# Analog.net
KiCad netlist of a schematic drawn in Altium Designer
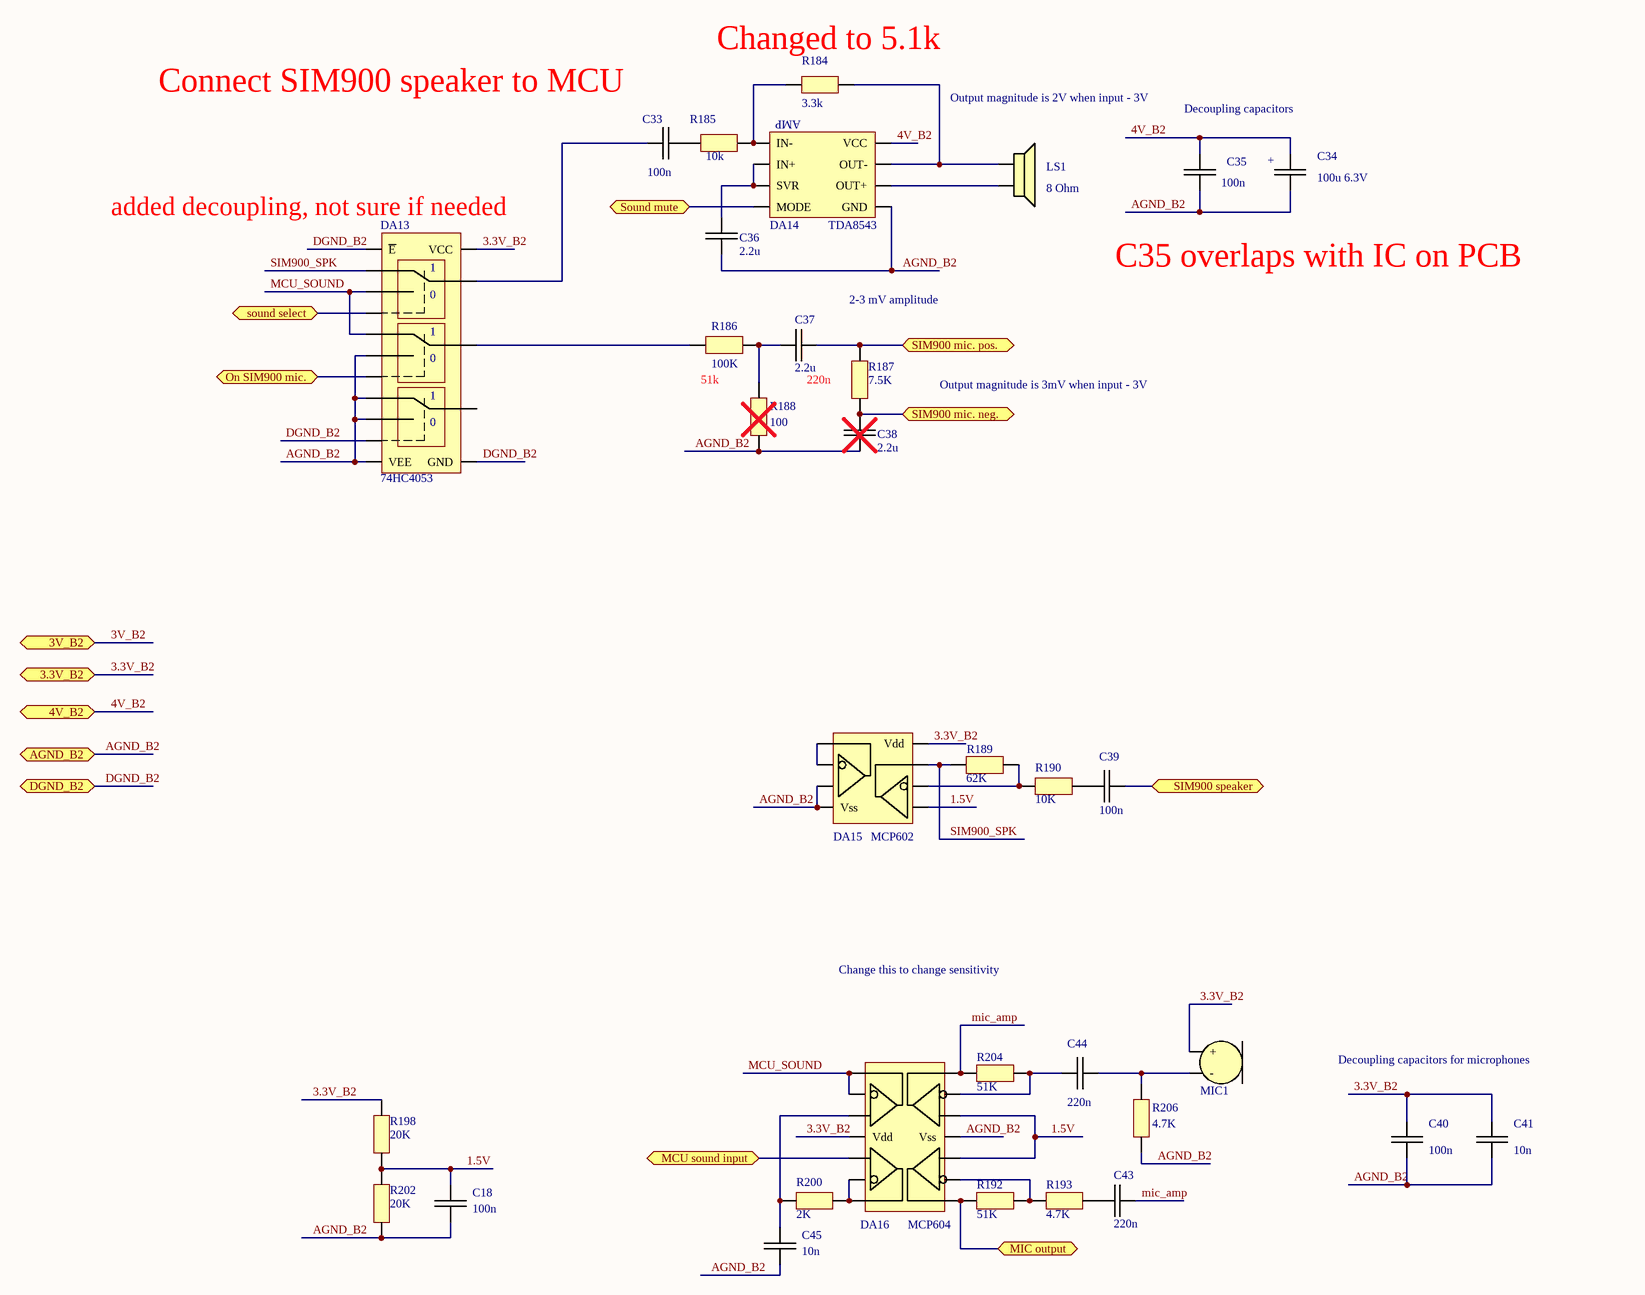
[diagram p0: Analog.SchDoc]

(export (version "E")
  (design (tool "Eeschema 10.0.6"))
  (components
    (comp (ref "C18") (value "100n") (footprint "0805") (libsource (lib "PRIM_fact") (part "C")))
    (comp (ref "C33") (value "100n") (footprint "0805") (libsource (lib "PRIM_fact") (part "C")))
    (comp (ref "C34")
      (value "100u 6.3V")
      (footprint "CALUM_SMD_C")
      (libsource (lib "PRIM_fact") (part "C_POL"))
    )
    (comp (ref "C35") (value "100n") (footprint "0805") (libsource (lib "PRIM_fact") (part "C")))
    (comp (ref "C36") (value "2.2u") (footprint "0805") (libsource (lib "PRIM_fact") (part "C")))
    (comp (ref "C37") (value "2.2u") (footprint "0805") (libsource (lib "PRIM_fact") (part "C")))
    (comp (ref "C38") (value "2.2u") (footprint "0805") (libsource (lib "PRIM_fact") (part "C")))
    (comp (ref "C39") (value "100n") (footprint "0805") (libsource (lib "PRIM_fact") (part "C")))
    (comp (ref "C40") (value "100n") (footprint "0805") (libsource (lib "PRIM_fact") (part "C")))
    (comp (ref "C41") (value "10n") (footprint "0805") (libsource (lib "PRIM_fact") (part "C")))
    (comp (ref "C43") (value "220n") (footprint "0805") (libsource (lib "PRIM_fact") (part "C")))
    (comp (ref "C44") (value "220n") (footprint "0805") (libsource (lib "PRIM_fact") (part "C")))
    (comp (ref "C45") (value "10n") (footprint "0805") (libsource (lib "PRIM_fact") (part "C")))
    (comp (ref "DA13") (value "74HC4053") (footprint "SOP16") (libsource (lib "IC_fact") (part "74HCx4053")))
    (comp (ref "DA14") (value "TDA8543") (footprint "SOP16") (libsource (lib "IC_fact") (part "TDA8543")))
    (comp (ref "DA15") (value "MCP602") (footprint "SOP8") (libsource (lib "IC_fact") (part "2xOP.AMP")))
    (comp (ref "DA16") (value "MCP604") (footprint "SOP14") (libsource (lib "IC_fact") (part "4xOP.AMP")))
    (comp (ref "LS1") (value "8 Ohm") (footprint "PLS_2") (libsource (lib "PRIM_fact") (part "Speaker")))
    (comp (ref "MIC1") (value "MIC") (footprint "MIC_6.0x5.2") (libsource (lib "PRIM_fact") (part "MIC")))
    (comp (ref "R184") (value "3.3k") (footprint "0805") (libsource (lib "") (part "R_1")))
    (comp (ref "R185") (value "10k") (footprint "0805") (libsource (lib "") (part "R_1")))
    (comp (ref "R186") (value "100K") (footprint "0805") (libsource (lib "") (part "R_2")))
    (comp (ref "R187") (value "7.5K") (footprint "0805") (libsource (lib "") (part "R_1")))
    (comp (ref "R188") (value "100") (footprint "0805") (libsource (lib "") (part "R_1")))
    (comp (ref "R189") (value "62K") (footprint "0805") (libsource (lib "") (part "R_1")))
    (comp (ref "R190") (value "10K") (footprint "0805") (libsource (lib "") (part "R_1")))
    (comp (ref "R192") (value "51K") (footprint "0805") (libsource (lib "") (part "R_2")))
    (comp (ref "R193") (value "4.7K") (footprint "0805") (libsource (lib "PRIM_fact") (part "R")))
    (comp (ref "R198") (value "20K") (footprint "0805") (libsource (lib "PRIM_fact") (part "R")))
    (comp (ref "R200") (value "2K") (footprint "0805") (libsource (lib "") (part "R_1")))
    (comp (ref "R202") (value "20K") (footprint "0805") (libsource (lib "PRIM_fact") (part "R")))
    (comp (ref "R204") (value "51K") (footprint "0805") (libsource (lib "") (part "R_2")))
    (comp (ref "R206") (value "4.7K") (footprint "0805") (libsource (lib "PRIM_fact") (part "R")))
  )
  (nets
    (net (code "1") (name "/1.5V") (class "Default")
      (node (ref "C18") (pin "2") (pintype "passive"))
      (node (ref "DA15") (pin "5") (pintype "passive"))
      (node (ref "DA16") (pin "10") (pintype "passive"))
      (node (ref "DA16") (pin "12") (pintype "passive"))
      (node (ref "R198") (pin "2") (pintype "passive"))
      (node (ref "R202") (pin "1") (pintype "passive"))
    )
    (net (code "2") (name "/3.3V_B2") (class "Default")
      (node (ref "C40") (pin "2") (pintype "passive"))
      (node (ref "C41") (pin "2") (pintype "passive"))
      (node (ref "DA13") (pin "16") (pinfunction "VCC_16") (pintype "passive"))
      (node (ref "DA15") (pin "8") (pinfunction "Vdd_8") (pintype "passive"))
      (node (ref "DA16") (pin "4") (pinfunction "Vdd_4") (pintype "passive"))
      (node (ref "MIC1") (pin "+") (pinfunction "+_+") (pintype "passive"))
      (node (ref "R198") (pin "1") (pintype "passive"))
    )
    (net (code "4") (name "/4V_B2") (class "Default")
      (node (ref "C34") (pin "1") (pintype "passive"))
      (node (ref "C35") (pin "2") (pintype "passive"))
      (node (ref "DA14") (pin "12") (pinfunction "VCC_12") (pintype "passive"))
    )
    (net (code "5") (name "/AGND_B2") (class "Default")
      (node (ref "C18") (pin "1") (pintype "passive"))
      (node (ref "C34") (pin "2") (pintype "passive"))
      (node (ref "C35") (pin "1") (pintype "passive"))
      (node (ref "C36") (pin "2") (pintype "passive"))
      (node (ref "C38") (pin "2") (pintype "passive"))
      (node (ref "C40") (pin "1") (pintype "passive"))
      (node (ref "C41") (pin "1") (pintype "passive"))
      (node (ref "C45") (pin "1") (pintype "passive"))
      (node (ref "DA13") (pin "12") (pintype "passive"))
      (node (ref "DA13") (pin "13") (pintype "passive"))
      (node (ref "DA13") (pin "5") (pintype "passive"))
      (node (ref "DA13") (pin "7") (pinfunction "VEE_7") (pintype "passive"))
      (node (ref "DA14") (pin "13") (pinfunction "GND_13") (pintype "passive"))
      (node (ref "DA15") (pin "3") (pintype "passive"))
      (node (ref "DA15") (pin "4") (pinfunction "Vss_4") (pintype "passive"))
      (node (ref "DA16") (pin "11") (pinfunction "Vss_11") (pintype "passive"))
      (node (ref "R188") (pin "2") (pintype "passive"))
      (node (ref "R202") (pin "2") (pintype "passive"))
      (node (ref "R206") (pin "2") (pintype "passive"))
    )
    (net (code "6") (name "/DGND_B2") (class "Default")
      (node (ref "DA13") (pin "11") (pintype "passive"))
      (node (ref "DA13") (pin "6") (pinfunction "~{E}_6") (pintype "passive"))
      (node (ref "DA13") (pin "8") (pinfunction "GND_8") (pintype "passive"))
    )
    (net (code "7") (name "/MCU sound input") (class "Default")
      (node (ref "DA16") (pin "5") (pintype "passive"))
    )
    (net (code "8") (name "/MCU_SOUND") (class "Default")
      (node (ref "DA13") (pin "2") (pintype "passive"))
      (node (ref "DA13") (pin "3") (pintype "passive"))
      (node (ref "DA16") (pin "1") (pintype "passive"))
      (node (ref "DA16") (pin "2") (pintype "passive"))
    )
    (net (code "9") (name "/MIC output") (class "Default")
      (node (ref "DA16") (pin "8") (pintype "passive"))
      (node (ref "R192") (pin "1") (pintype "passive"))
    )
    (net (code "10") (name "/On SIM900 mic.") (class "Default")
      (node (ref "DA13") (pin "9") (pintype "passive"))
    )
    (net (code "11") (name "/SIM900 mic. neg.") (class "Default")
      (node (ref "C38") (pin "1") (pintype "passive"))
      (node (ref "R187") (pin "2") (pintype "passive"))
    )
    (net (code "12") (name "/SIM900 mic. pos.") (class "Default")
      (node (ref "C37") (pin "1") (pintype "passive"))
      (node (ref "R187") (pin "1") (pintype "passive"))
    )
    (net (code "13") (name "/SIM900 speaker") (class "Default")
      (node (ref "C39") (pin "2") (pintype "passive"))
    )
    (net (code "14") (name "/SIM900_SPK") (class "Default")
      (node (ref "DA13") (pin "1") (pintype "passive"))
      (node (ref "DA15") (pin "7") (pintype "passive"))
      (node (ref "R189") (pin "2") (pintype "passive"))
    )
    (net (code "15") (name "/Sound mute") (class "Default")
      (node (ref "DA14") (pin "3") (pinfunction "MODE_3") (pintype "passive"))
    )
    (net (code "16") (name "/mic_amp") (class "Default")
      (node (ref "C43") (pin "2") (pintype "passive"))
      (node (ref "DA16") (pin "14") (pintype "passive"))
      (node (ref "R204") (pin "1") (pintype "passive"))
    )
    (net (code "17") (name "/sound select") (class "Default")
      (node (ref "DA13") (pin "10") (pintype "passive"))
    )
    (net (code "18") (name "Net-(C33-Pad1)") (class "Default")
      (node (ref "C33") (pin "1") (pintype "passive"))
      (node (ref "DA13") (pin "15") (pintype "passive"))
    )
    (net (code "19") (name "Net-(C33-Pad2)") (class "Default")
      (node (ref "C33") (pin "2") (pintype "passive"))
      (node (ref "R185") (pin "2") (pintype "passive"))
    )
    (net (code "20") (name "Net-(C37-Pad2)") (class "Default")
      (node (ref "C37") (pin "2") (pintype "passive"))
      (node (ref "R186") (pin "2") (pintype "passive"))
      (node (ref "R188") (pin "1") (pintype "passive"))
    )
    (net (code "21") (name "Net-(C39-Pad1)") (class "Default")
      (node (ref "C39") (pin "1") (pintype "passive"))
      (node (ref "R190") (pin "1") (pintype "passive"))
    )
    (net (code "22") (name "Net-(C43-Pad1)") (class "Default")
      (node (ref "C43") (pin "1") (pintype "passive"))
      (node (ref "R193") (pin "1") (pintype "passive"))
    )
    (net (code "23") (name "Net-(C44-Pad1)") (class "Default")
      (node (ref "C44") (pin "1") (pintype "passive"))
      (node (ref "DA16") (pin "13") (pintype "passive"))
      (node (ref "R204") (pin "2") (pintype "passive"))
    )
    (net (code "24") (name "Net-(C44-Pad2)") (class "Default")
      (node (ref "C44") (pin "2") (pintype "passive"))
      (node (ref "MIC1") (pin "-") (pinfunction "-_-") (pintype "passive"))
      (node (ref "R206") (pin "1") (pintype "passive"))
    )
    (net (code "25") (name "Net-(C45-Pad2)") (class "Default")
      (node (ref "C45") (pin "2") (pintype "passive"))
      (node (ref "DA16") (pin "3") (pintype "passive"))
      (node (ref "R200") (pin "2") (pintype "passive"))
    )
    (net (code "26") (name "Net-(DA13-Pad4)") (class "Default")
      (node (ref "DA13") (pin "4") (pintype "passive"))
      (node (ref "R186") (pin "1") (pintype "passive"))
    )
    (net (code "27") (name "Net-(DA14-IN+)") (class "Default")
      (node (ref "C36") (pin "1") (pintype "passive"))
      (node (ref "DA14") (pin "4") (pinfunction "SVR_4") (pintype "passive"))
      (node (ref "DA14") (pin "5") (pinfunction "IN+_5") (pintype "passive"))
    )
    (net (code "28") (name "Net-(DA14-IN-)") (class "Default")
      (node (ref "DA14") (pin "6") (pinfunction "IN-_6") (pintype "passive"))
      (node (ref "R184") (pin "2") (pintype "passive"))
      (node (ref "R185") (pin "1") (pintype "passive"))
    )
    (net (code "29") (name "Net-(DA14-OUT+)") (class "Default")
      (node (ref "DA14") (pin "14") (pinfunction "OUT+_14") (pintype "passive"))
      (node (ref "LS1") (pin "2") (pintype "passive"))
    )
    (net (code "30") (name "Net-(DA14-OUT-)") (class "Default")
      (node (ref "DA14") (pin "11") (pinfunction "OUT-_11") (pintype "passive"))
      (node (ref "LS1") (pin "1") (pintype "passive"))
      (node (ref "R184") (pin "1") (pintype "passive"))
    )
    (net (code "31") (name "Net-(DA15-Pad1)") (class "Default")
      (node (ref "DA15") (pin "1") (pintype "passive"))
      (node (ref "DA15") (pin "2") (pintype "passive"))
    )
    (net (code "32") (name "Net-(DA15-Pad6)") (class "Default")
      (node (ref "DA15") (pin "6") (pintype "passive"))
      (node (ref "R189") (pin "1") (pintype "passive"))
      (node (ref "R190") (pin "2") (pintype "passive"))
    )
    (net (code "33") (name "Net-(DA16-Pad6)") (class "Default")
      (node (ref "DA16") (pin "6") (pintype "passive"))
      (node (ref "DA16") (pin "7") (pintype "passive"))
      (node (ref "R200") (pin "1") (pintype "passive"))
    )
    (net (code "34") (name "Net-(DA16-Pad9)") (class "Default")
      (node (ref "DA16") (pin "9") (pintype "passive"))
      (node (ref "R192") (pin "2") (pintype "passive"))
      (node (ref "R193") (pin "2") (pintype "passive"))
    )
    (net (code "35") (name "unconnected-(DA13-Pad14)") (class "Default")
      (node (ref "DA13") (pin "14") (pintype "passive"))
    )
  )
)
